# ctrlr_w_ST7735.net
KiCad netlist of a schematic drawn in EAGLE
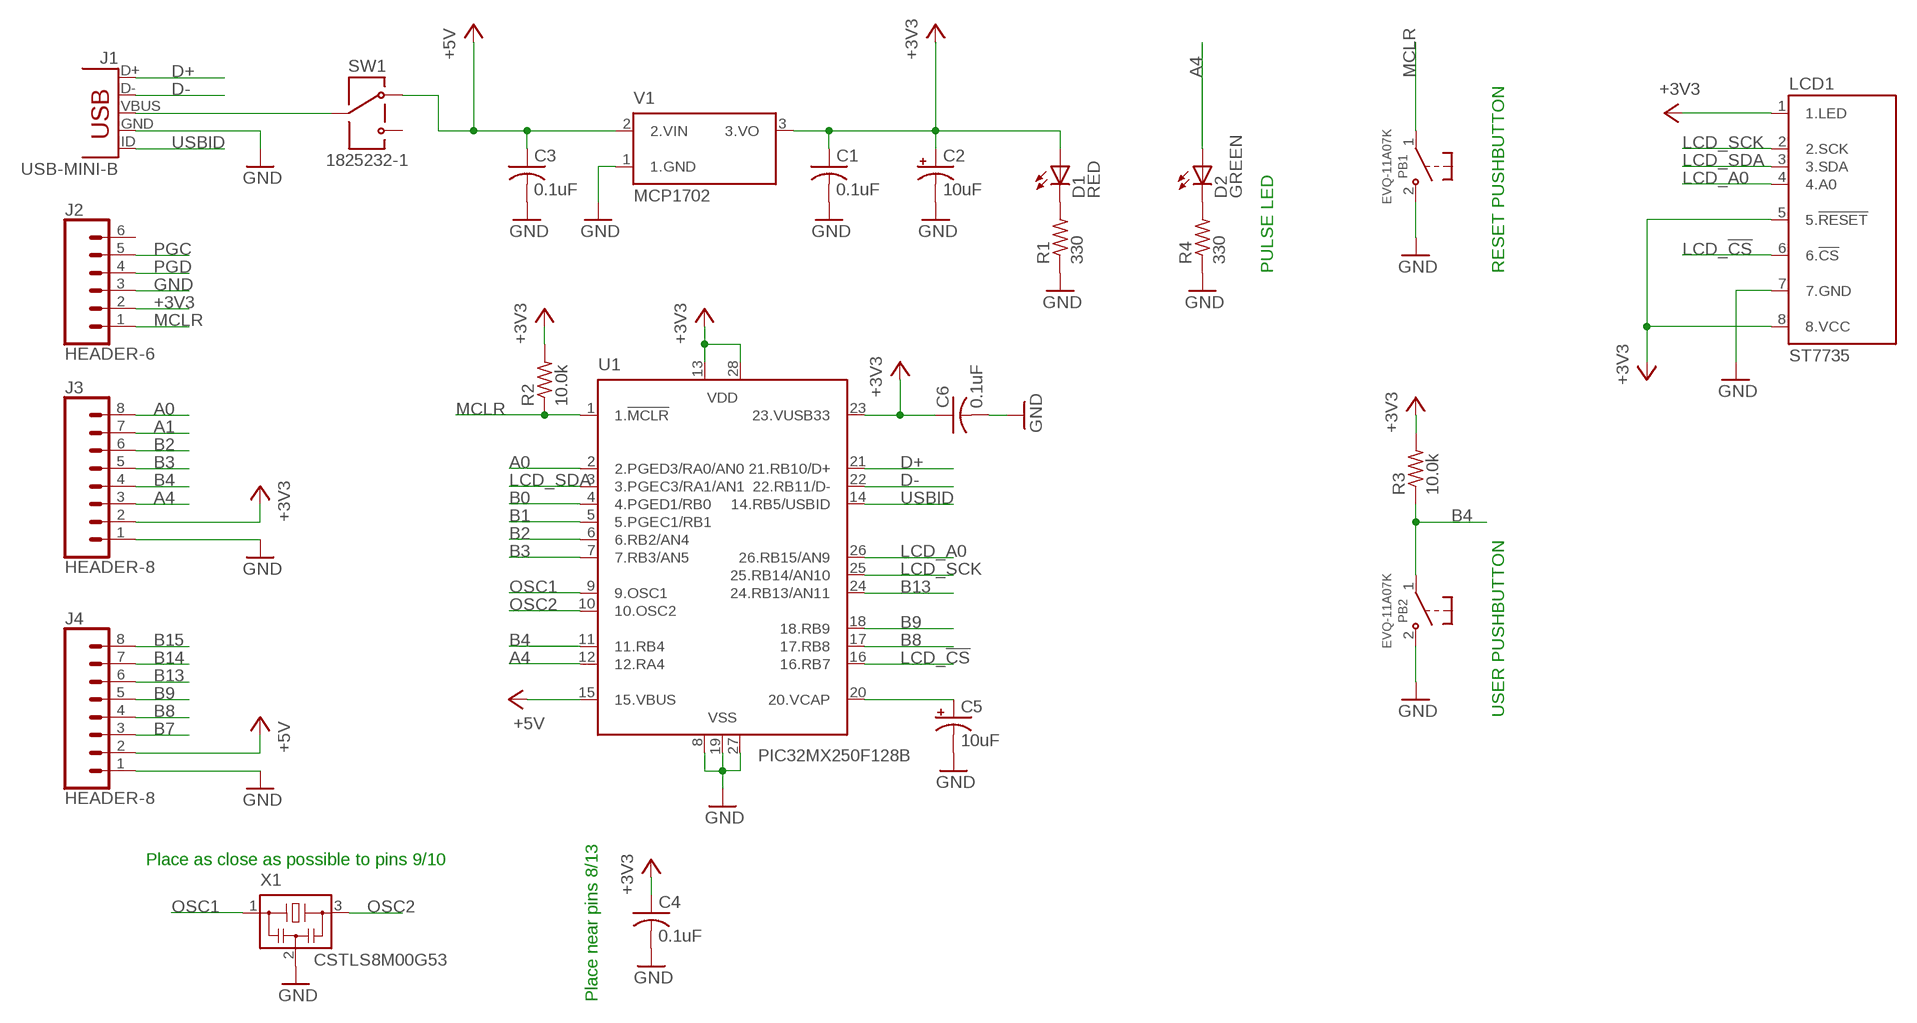
[diagram p0: schematic, sheet 1]

(export (version "E")
  (design (tool "Eeschema 10.0.6"))
  (components
    (comp (ref "C1")
      (value "0.1uF")
      (footprint "eagle-import:C1206")
      (libsource (lib "eagle-import") (part "C-USC1206"))
    )
    (comp (ref "C2")
      (value "10uF")
      (footprint "eagle-import:TAP5-50")
      (libsource (lib "eagle-import") (part "CPOL-USTAP5-50"))
    )
    (comp (ref "C3")
      (value "0.1uF")
      (footprint "eagle-import:C1206")
      (libsource (lib "eagle-import") (part "C-USC1206"))
    )
    (comp (ref "C4")
      (value "0.1uF")
      (footprint "eagle-import:C1206")
      (libsource (lib "eagle-import") (part "C-USC1206"))
    )
    (comp (ref "C5")
      (value "10uF")
      (footprint "eagle-import:TAP5-50")
      (libsource (lib "eagle-import") (part "CPOL-USTAP5-50"))
    )
    (comp (ref "C6")
      (value "0.1uF")
      (footprint "eagle-import:C1206")
      (libsource (lib "eagle-import") (part "C-USC1206"))
    )
    (comp (ref "D1")
      (value "LED-RED")
      (footprint "eagle-import:LED-3MM-V")
      (libsource (lib "eagle-import") (part "LED-RED"))
    )
    (comp (ref "D2")
      (value "LED-GREEN")
      (footprint "eagle-import:LED-3MM-V")
      (libsource (lib "eagle-import") (part "LED-GREEN"))
    )
    (comp (ref "J1")
      (value "USB-MINI-B")
      (footprint "eagle-import:USB-MB-TO")
      (libsource (lib "eagle-import") (part "USB-MINI-B"))
    )
    (comp (ref "J2")
      (value "HEADER-6")
      (footprint "eagle-import:CONN_1X06")
      (libsource (lib "eagle-import") (part "HEADER-6"))
    )
    (comp (ref "J3")
      (value "HEADER-8")
      (footprint "eagle-import:CONN_1X08")
      (libsource (lib "eagle-import") (part "HEADER-8"))
    )
    (comp (ref "J4")
      (value "HEADER-8")
      (footprint "eagle-import:CONN_1X08")
      (libsource (lib "eagle-import") (part "HEADER-8"))
    )
    (comp (ref "LCD1")
      (value "ST7735")
      (footprint "eagle-import:DISPLAY")
      (libsource (lib "eagle-import") (part "ST7735"))
    )
    (comp (ref "PB1")
      (value "EVQ-11A07K")
      (footprint "eagle-import:PCPIN-2")
      (libsource (lib "eagle-import") (part "EVQ-11A07K"))
    )
    (comp (ref "PB2")
      (value "EVQ-11A07K")
      (footprint "eagle-import:PCPIN-2")
      (libsource (lib "eagle-import") (part "EVQ-11A07K"))
    )
    (comp (ref "R1")
      (value "330")
      (footprint "eagle-import:R1206")
      (libsource (lib "eagle-import") (part "R-US_R1206"))
    )
    (comp (ref "R2")
      (value "10.0k")
      (footprint "eagle-import:R1206")
      (libsource (lib "eagle-import") (part "R-US_R1206"))
    )
    (comp (ref "R3")
      (value "10.0k")
      (footprint "eagle-import:R1206")
      (libsource (lib "eagle-import") (part "R-US_R1206"))
    )
    (comp (ref "R4")
      (value "330")
      (footprint "eagle-import:R1206")
      (libsource (lib "eagle-import") (part "R-US_R1206"))
    )
    (comp (ref "SW1")
      (value "1825232-1")
      (footprint "eagle-import:PCPIN-3SS")
      (libsource (lib "eagle-import") (part "1825232-1"))
    )
    (comp (ref "U1")
      (value "PIC32MX250F128B")
      (footprint "eagle-import:DIP28-3")
      (libsource (lib "eagle-import") (part "PIC32MX250F128B"))
    )
    (comp (ref "V1")
      (value "MCP1702")
      (footprint "eagle-import:TO-92")
      (libsource (lib "eagle-import") (part "MCP1702"))
    )
    (comp (ref "X1")
      (value "CSTLS8M00G53")
      (footprint "eagle-import:RAD-3-2.5")
      (libsource (lib "eagle-import") (part "CSTLS8M00G53"))
    )
  )
  (nets
    (net (code "1") (name "+3V3") (class "Default")
      (node (ref "C1") (pin "1") (pinfunction "1_1") (pintype "passive"))
      (node (ref "C2") (pin "+") (pinfunction "+_+") (pintype "passive"))
      (node (ref "C4") (pin "1") (pinfunction "1_1") (pintype "passive"))
      (node (ref "C6") (pin "1") (pinfunction "1_1") (pintype "passive"))
      (node (ref "D1") (pin "A") (pinfunction "A_A") (pintype "passive"))
      (node (ref "J2") (pin "2") (pinfunction "2._2") (pintype "passive"))
      (node (ref "J3") (pin "2") (pinfunction "2._2") (pintype "passive"))
      (node (ref "LCD1") (pin "1") (pinfunction "1.LED_1") (pintype "bidirectional"))
      (node (ref "LCD1") (pin "5") (pinfunction "5.~{RESET}_5") (pintype "bidirectional"))
      (node (ref "LCD1") (pin "8") (pinfunction "8.VCC_8") (pintype "bidirectional"))
      (node (ref "R2") (pin "2") (pinfunction "2_2") (pintype "passive"))
      (node (ref "R3") (pin "2") (pinfunction "2_2") (pintype "passive"))
      (node (ref "U1") (pin "13") (pinfunction "13.VDD_13") (pintype "power_in"))
      (node (ref "U1") (pin "23") (pinfunction "23.VUSB33_23") (pintype "bidirectional"))
      (node (ref "U1") (pin "28") (pinfunction "28.AVDD_28") (pintype "power_in"))
      (node (ref "V1") (pin "3") (pinfunction "3.VO_3") (pintype "output"))
    )
    (net (code "2") (name "+5V") (class "Default")
      (node (ref "C3") (pin "1") (pinfunction "1_1") (pintype "passive"))
      (node (ref "J4") (pin "2") (pinfunction "2._2") (pintype "passive"))
      (node (ref "SW1") (pin "1") (pinfunction "1_1") (pintype "bidirectional"))
      (node (ref "U1") (pin "15") (pinfunction "15.VBUS_15") (pintype "bidirectional"))
      (node (ref "V1") (pin "2") (pinfunction "2.VIN_2") (pintype "input"))
    )
    (net (code "3") (name "/A0") (class "Default")
      (node (ref "J3") (pin "8") (pinfunction "8._8") (pintype "passive"))
      (node (ref "U1") (pin "2") (pinfunction "2.PGED3/RA0/AN0_2") (pintype "bidirectional"))
    )
    (net (code "4") (name "/A1") (class "Default")
      (node (ref "J3") (pin "7") (pinfunction "7._7") (pintype "passive"))
    )
    (net (code "5") (name "/A4") (class "Default")
      (node (ref "D2") (pin "A") (pinfunction "A_A") (pintype "passive"))
      (node (ref "J3") (pin "3") (pinfunction "3._3") (pintype "passive"))
      (node (ref "U1") (pin "12") (pinfunction "12.RA4_12") (pintype "bidirectional"))
    )
    (net (code "6") (name "/B0") (class "Default")
      (node (ref "U1") (pin "4") (pinfunction "4.PGED1/RB0_4") (pintype "bidirectional"))
    )
    (net (code "7") (name "/B1") (class "Default")
      (node (ref "U1") (pin "5") (pinfunction "5.PGEC1/RB1_5") (pintype "bidirectional"))
    )
    (net (code "8") (name "/B2") (class "Default")
      (node (ref "J3") (pin "6") (pinfunction "6._6") (pintype "passive"))
      (node (ref "U1") (pin "6") (pinfunction "6.RB2/AN4_6") (pintype "bidirectional"))
    )
    (net (code "9") (name "/B3") (class "Default")
      (node (ref "J3") (pin "5") (pinfunction "5._5") (pintype "passive"))
      (node (ref "U1") (pin "7") (pinfunction "7.RB3/AN5_7") (pintype "bidirectional"))
    )
    (net (code "10") (name "/B4") (class "Default")
      (node (ref "J3") (pin "4") (pinfunction "4._4") (pintype "passive"))
      (node (ref "PB2") (pin "1") (pinfunction "1.A_1") (pintype "bidirectional"))
      (node (ref "R3") (pin "1") (pinfunction "1_1") (pintype "passive"))
      (node (ref "U1") (pin "11") (pinfunction "11.RB4_11") (pintype "bidirectional"))
    )
    (net (code "11") (name "/B7") (class "Default")
      (node (ref "J4") (pin "3") (pinfunction "3._3") (pintype "passive"))
    )
    (net (code "12") (name "/B8") (class "Default")
      (node (ref "J4") (pin "4") (pinfunction "4._4") (pintype "passive"))
      (node (ref "U1") (pin "17") (pinfunction "17.RB8_17") (pintype "bidirectional"))
    )
    (net (code "13") (name "/B9") (class "Default")
      (node (ref "J4") (pin "5") (pinfunction "5._5") (pintype "passive"))
      (node (ref "U1") (pin "18") (pinfunction "18.RB9_18") (pintype "bidirectional"))
    )
    (net (code "14") (name "/B13") (class "Default")
      (node (ref "J4") (pin "6") (pinfunction "6._6") (pintype "passive"))
      (node (ref "U1") (pin "24") (pinfunction "24.RB13/AN11_24") (pintype "bidirectional"))
    )
    (net (code "15") (name "/B14") (class "Default")
      (node (ref "J4") (pin "7") (pinfunction "7._7") (pintype "passive"))
    )
    (net (code "16") (name "/B15") (class "Default")
      (node (ref "J4") (pin "8") (pinfunction "8._8") (pintype "passive"))
    )
    (net (code "17") (name "/D+") (class "Default")
      (node (ref "J1") (pin "D+") (pinfunction "D+_D+") (pintype "bidirectional"))
      (node (ref "U1") (pin "21") (pinfunction "21.RB10/D+_21") (pintype "bidirectional"))
    )
    (net (code "18") (name "/D-") (class "Default")
      (node (ref "J1") (pin "D-") (pinfunction "D-_D-") (pintype "bidirectional"))
      (node (ref "U1") (pin "22") (pinfunction "22.RB11/D-_22") (pintype "bidirectional"))
    )
    (net (code "19") (name "/LCD_A0") (class "Default")
      (node (ref "LCD1") (pin "4") (pinfunction "4.A0_4") (pintype "bidirectional"))
      (node (ref "U1") (pin "26") (pinfunction "26.RB15/AN9_26") (pintype "bidirectional"))
    )
    (net (code "20") (name "/LCD_SCK") (class "Default")
      (node (ref "LCD1") (pin "2") (pinfunction "2.SCK_2") (pintype "bidirectional"))
      (node (ref "U1") (pin "25") (pinfunction "25.RB14/AN10_25") (pintype "bidirectional"))
    )
    (net (code "21") (name "/LCD_SDA") (class "Default")
      (node (ref "LCD1") (pin "3") (pinfunction "3.SDA_3") (pintype "bidirectional"))
      (node (ref "U1") (pin "3") (pinfunction "3.PGEC3/RA1/AN1_3") (pintype "bidirectional"))
    )
    (net (code "22") (name "/LCD_~{CS}") (class "Default")
      (node (ref "LCD1") (pin "6") (pinfunction "6.~{CS}_6") (pintype "bidirectional"))
      (node (ref "U1") (pin "16") (pinfunction "16.RB7_16") (pintype "bidirectional"))
    )
    (net (code "23") (name "/MCLR") (class "Default")
      (node (ref "J2") (pin "1") (pinfunction "1._1") (pintype "passive"))
      (node (ref "PB1") (pin "1") (pinfunction "1.A_1") (pintype "bidirectional"))
      (node (ref "R2") (pin "1") (pinfunction "1_1") (pintype "passive"))
      (node (ref "U1") (pin "1") (pinfunction "1.~{MCLR}_1") (pintype "input"))
    )
    (net (code "24") (name "/OSC1") (class "Default")
      (node (ref "U1") (pin "9") (pinfunction "9.OSC1_9") (pintype "input"))
      (node (ref "X1") (pin "1") (pinfunction "1_1") (pintype "passive"))
    )
    (net (code "25") (name "/OSC2") (class "Default")
      (node (ref "U1") (pin "10") (pinfunction "10.OSC2_10") (pintype "output"))
      (node (ref "X1") (pin "3") (pinfunction "3_3") (pintype "passive"))
    )
    (net (code "26") (name "/PGC") (class "Default")
      (node (ref "J2") (pin "5") (pinfunction "5._5") (pintype "passive"))
    )
    (net (code "27") (name "/PGD") (class "Default")
      (node (ref "J2") (pin "4") (pinfunction "4._4") (pintype "passive"))
    )
    (net (code "28") (name "/USBID") (class "Default")
      (node (ref "J1") (pin "ID") (pinfunction "ID_ID") (pintype "bidirectional"))
      (node (ref "U1") (pin "14") (pinfunction "14.RB5/USBID_14") (pintype "bidirectional"))
    )
    (net (code "29") (name "GND") (class "Default")
      (node (ref "C1") (pin "2") (pinfunction "2_2") (pintype "passive"))
      (node (ref "C2") (pin "-") (pinfunction "-_-") (pintype "passive"))
      (node (ref "C3") (pin "2") (pinfunction "2_2") (pintype "passive"))
      (node (ref "C4") (pin "2") (pinfunction "2_2") (pintype "passive"))
      (node (ref "C5") (pin "-") (pinfunction "-_-") (pintype "passive"))
      (node (ref "C6") (pin "2") (pinfunction "2_2") (pintype "passive"))
      (node (ref "J1") (pin "GND") (pinfunction "GND_GND") (pintype "bidirectional"))
      (node (ref "J2") (pin "3") (pinfunction "3._3") (pintype "passive"))
      (node (ref "J3") (pin "1") (pinfunction "1._1") (pintype "passive"))
      (node (ref "J4") (pin "1") (pinfunction "1._1") (pintype "passive"))
      (node (ref "LCD1") (pin "7") (pinfunction "7.GND_7") (pintype "bidirectional"))
      (node (ref "PB1") (pin "2") (pinfunction "2.B_2") (pintype "bidirectional"))
      (node (ref "PB2") (pin "2") (pinfunction "2.B_2") (pintype "bidirectional"))
      (node (ref "R1") (pin "1") (pinfunction "1_1") (pintype "passive"))
      (node (ref "R4") (pin "1") (pinfunction "1_1") (pintype "passive"))
      (node (ref "U1") (pin "19") (pinfunction "19.VSS_19") (pintype "power_in"))
      (node (ref "U1") (pin "27") (pinfunction "27.AVSS_27") (pintype "bidirectional"))
      (node (ref "U1") (pin "8") (pinfunction "8.VSS_8") (pintype "power_in"))
      (node (ref "V1") (pin "1") (pinfunction "1.GND_1") (pintype "passive"))
      (node (ref "X1") (pin "2") (pinfunction "2_2") (pintype "passive"))
    )
    (net (code "30") (name "Net-(D1-C)") (class "Default")
      (node (ref "D1") (pin "K") (pinfunction "C_K") (pintype "passive"))
      (node (ref "R1") (pin "2") (pinfunction "2_2") (pintype "passive"))
    )
    (net (code "31") (name "Net-(D2-C)") (class "Default")
      (node (ref "D2") (pin "K") (pinfunction "C_K") (pintype "passive"))
      (node (ref "R4") (pin "2") (pinfunction "2_2") (pintype "passive"))
    )
    (net (code "32") (name "Net-(J1-PadVBUS)") (class "Default")
      (node (ref "J1") (pin "VBUS") (pinfunction "VBUS_VBUS") (pintype "bidirectional"))
      (node (ref "SW1") (pin "2") (pinfunction "2_2") (pintype "bidirectional"))
    )
    (net (code "33") (name "Net-(U1-20.VCAP)") (class "Default")
      (node (ref "C5") (pin "+") (pinfunction "+_+") (pintype "passive"))
      (node (ref "U1") (pin "20") (pinfunction "20.VCAP_20") (pintype "bidirectional"))
    )
    (net (code "34") (name "unconnected-(J2-6.-Pad6)") (class "Default")
      (node (ref "J2") (pin "6") (pinfunction "6._6") (pintype "passive"))
    )
    (net (code "35") (name "unconnected-(SW1-Pad3)") (class "Default")
      (node (ref "SW1") (pin "3") (pinfunction "3_3") (pintype "bidirectional"))
    )
  )
)
